# CI_Server_Wiring.net
KiCad netlist of a schematic drawn in EAGLE
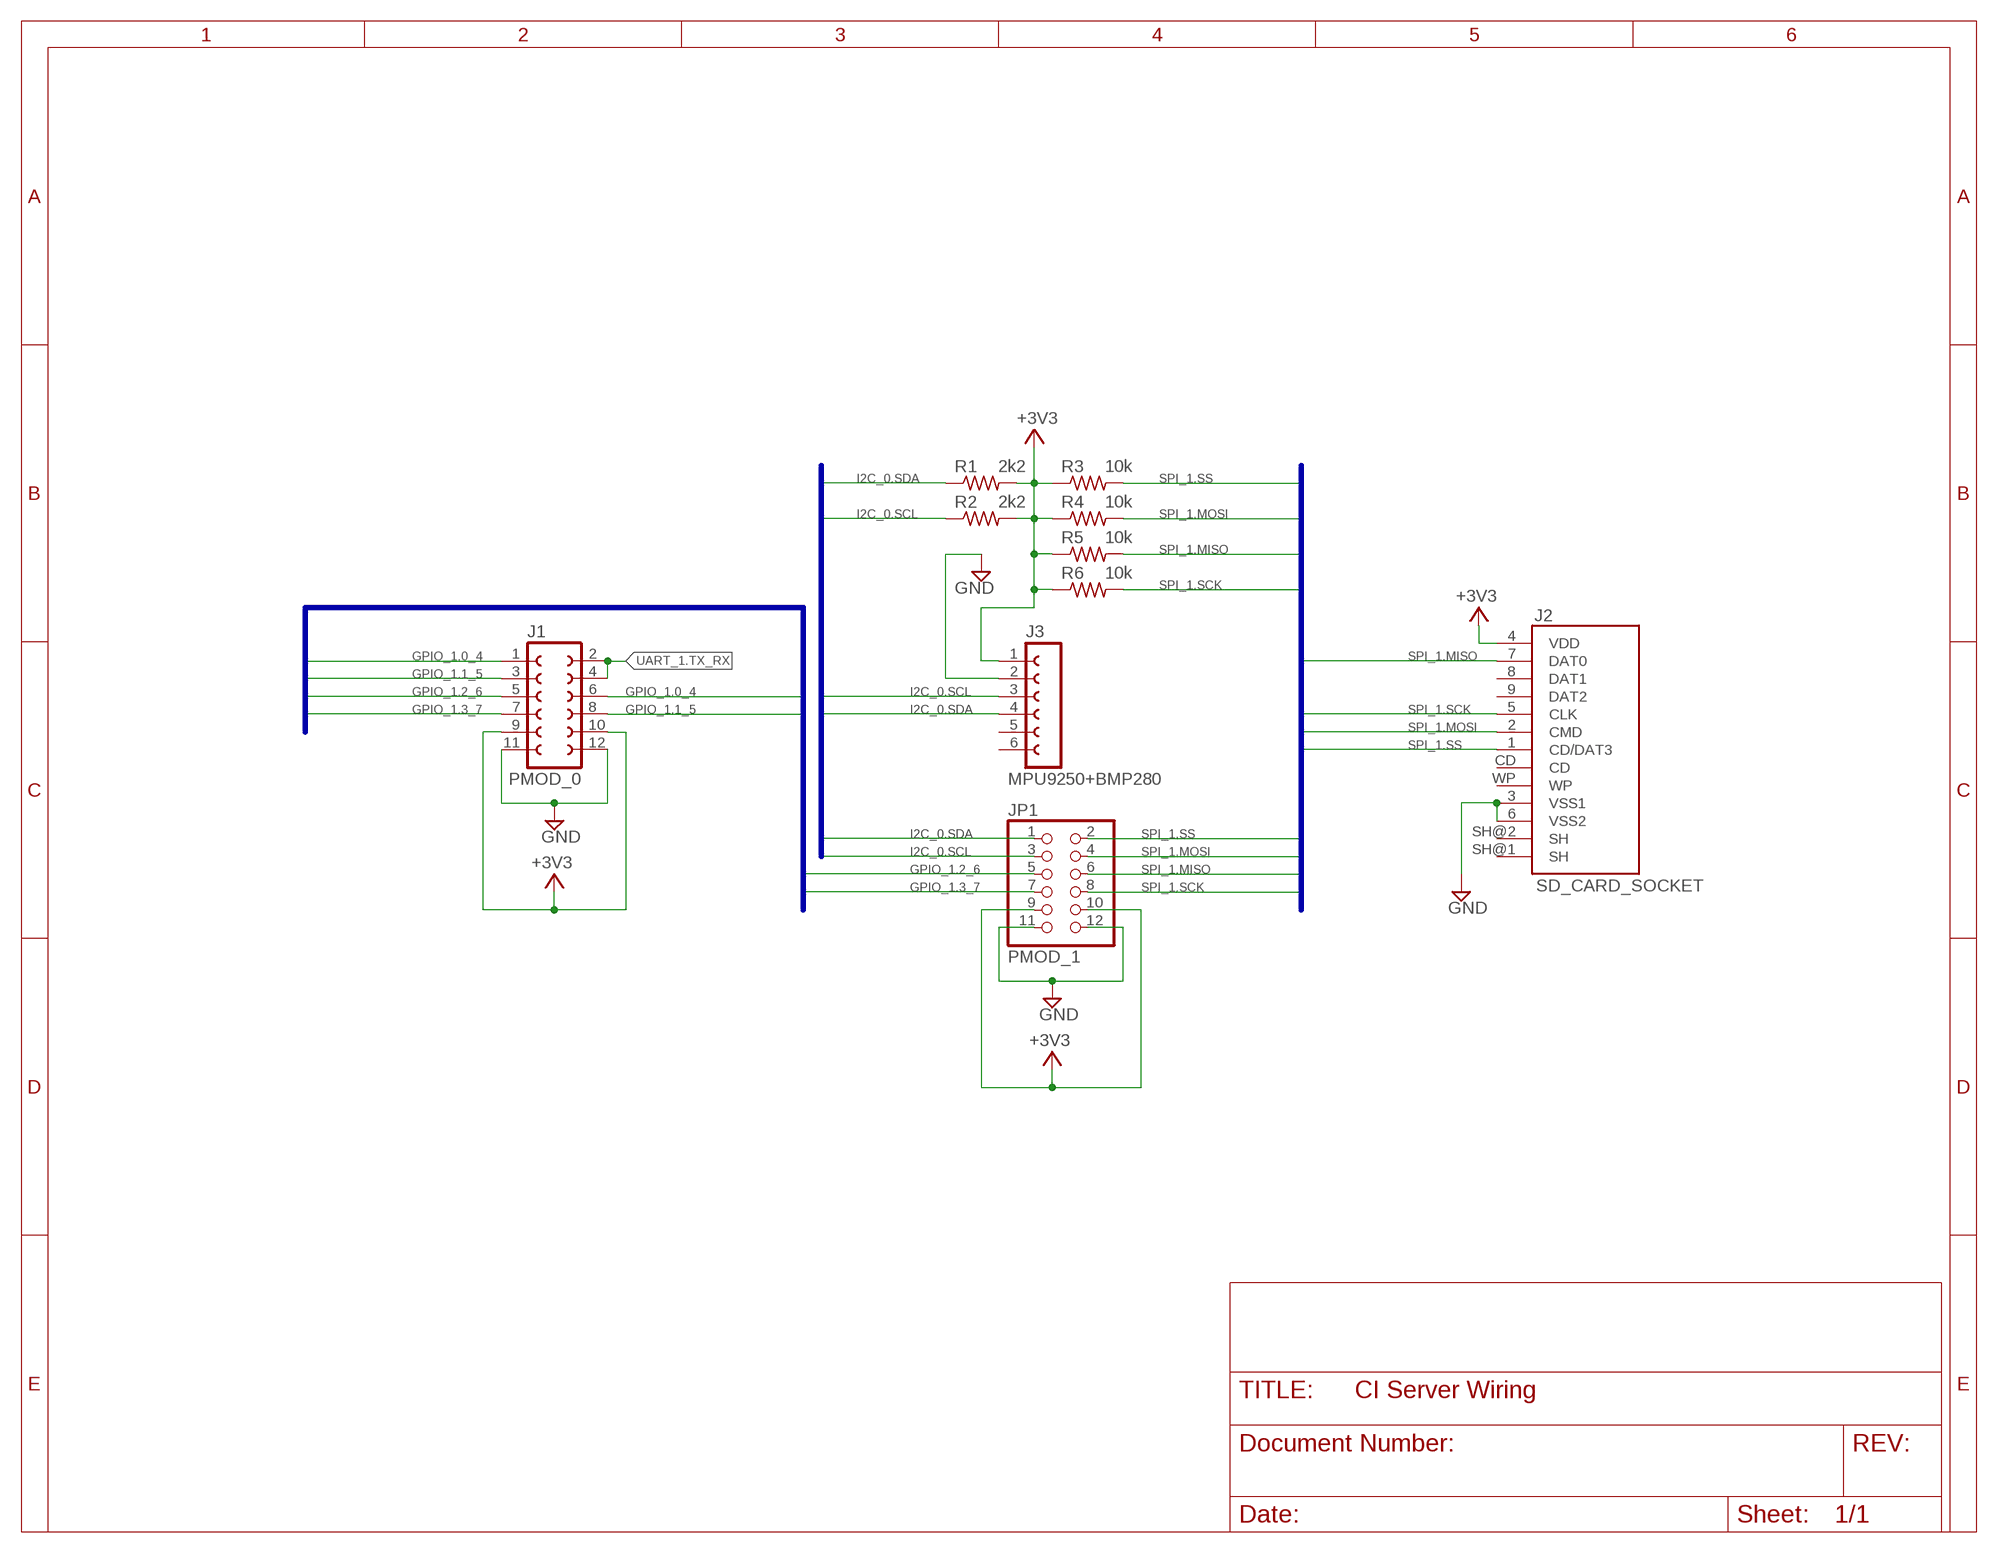
[diagram p0: schematic, sheet 1]

(export (version "E")
  (design (tool "Eeschema 10.0.6"))
  (components
    (comp (ref "J1")
      (value "PMOD_0")
      (footprint "eagle-import:FE06-2W")
      (libsource (lib "eagle-import") (part "FE06-2W"))
    )
    (comp (ref "J2")
      (value "SD_CARD_SOCKET")
      (footprint "eagle-import:SD")
      (libsource (lib "eagle-import") (part "SD_CARD_SOCKET"))
    )
    (comp (ref "J3")
      (value "MPU9250+BMP280")
      (footprint "eagle-import:FE06")
      (libsource (lib "eagle-import") (part "FE06-1"))
    )
    (comp (ref "JP1")
      (value "PMOD_1")
      (footprint "eagle-import:2X06_90")
      (libsource (lib "eagle-import") (part "PINHD-2X6/90"))
    )
    (comp (ref "R1")
      (value "2k2")
      (footprint "eagle-import:0309_12")
      (libsource (lib "eagle-import") (part "R-US_0309/12"))
    )
    (comp (ref "R2")
      (value "2k2")
      (footprint "eagle-import:0309_12")
      (libsource (lib "eagle-import") (part "R-US_0309/12"))
    )
    (comp (ref "R3")
      (value "10k")
      (footprint "eagle-import:0309_12")
      (libsource (lib "eagle-import") (part "R-US_0309/12"))
    )
    (comp (ref "R4")
      (value "10k")
      (footprint "eagle-import:0309_12")
      (libsource (lib "eagle-import") (part "R-US_0309/12"))
    )
    (comp (ref "R5")
      (value "10k")
      (footprint "eagle-import:0309_12")
      (libsource (lib "eagle-import") (part "R-US_0309/12"))
    )
    (comp (ref "R6")
      (value "10k")
      (footprint "eagle-import:0309_12")
      (libsource (lib "eagle-import") (part "R-US_0309/12"))
    )
  )
  (nets
    (net (code "1") (name "+3V3") (class "Default")
      (node (ref "J1") (pin "10") (pinfunction "10_10") (pintype "passive"))
      (node (ref "J1") (pin "9") (pinfunction "9_9") (pintype "passive"))
      (node (ref "J2") (pin "4") (pinfunction "VDD_4") (pintype "power_in"))
      (node (ref "J3") (pin "1") (pinfunction "1_1") (pintype "passive"))
      (node (ref "JP1") (pin "10") (pinfunction "10_10") (pintype "passive"))
      (node (ref "JP1") (pin "9") (pinfunction "9_9") (pintype "passive"))
      (node (ref "R1") (pin "2") (pinfunction "2_2") (pintype "passive"))
      (node (ref "R2") (pin "2") (pinfunction "2_2") (pintype "passive"))
      (node (ref "R3") (pin "1") (pinfunction "1_1") (pintype "passive"))
      (node (ref "R4") (pin "1") (pinfunction "1_1") (pintype "passive"))
      (node (ref "R5") (pin "1") (pinfunction "1_1") (pintype "passive"))
      (node (ref "R6") (pin "1") (pinfunction "1_1") (pintype "passive"))
    )
    (net (code "2") (name "/GPIO_1.0_4") (class "Default")
      (node (ref "J1") (pin "1") (pinfunction "1_1") (pintype "passive"))
      (node (ref "J1") (pin "6") (pinfunction "6_6") (pintype "passive"))
    )
    (net (code "3") (name "/GPIO_1.1_5") (class "Default")
      (node (ref "J1") (pin "3") (pinfunction "3_3") (pintype "passive"))
      (node (ref "J1") (pin "8") (pinfunction "8_8") (pintype "passive"))
    )
    (net (code "4") (name "/GPIO_1.2_6") (class "Default")
      (node (ref "J1") (pin "5") (pinfunction "5_5") (pintype "passive"))
      (node (ref "JP1") (pin "5") (pinfunction "5_5") (pintype "passive"))
    )
    (net (code "5") (name "/GPIO_1.3_7") (class "Default")
      (node (ref "J1") (pin "7") (pinfunction "7_7") (pintype "passive"))
      (node (ref "JP1") (pin "7") (pinfunction "7_7") (pintype "passive"))
    )
    (net (code "6") (name "/I2C_0.SCL") (class "Default")
      (node (ref "J3") (pin "3") (pinfunction "3_3") (pintype "passive"))
      (node (ref "JP1") (pin "3") (pinfunction "3_3") (pintype "passive"))
      (node (ref "R2") (pin "1") (pinfunction "1_1") (pintype "passive"))
    )
    (net (code "7") (name "/I2C_0.SDA") (class "Default")
      (node (ref "J3") (pin "4") (pinfunction "4_4") (pintype "passive"))
      (node (ref "JP1") (pin "1") (pinfunction "1_1") (pintype "passive"))
      (node (ref "R1") (pin "1") (pinfunction "1_1") (pintype "passive"))
    )
    (net (code "8") (name "/SPI_1.MISO") (class "Default")
      (node (ref "J2") (pin "7") (pinfunction "DAT0_7") (pintype "bidirectional"))
      (node (ref "JP1") (pin "6") (pinfunction "6_6") (pintype "passive"))
      (node (ref "R5") (pin "2") (pinfunction "2_2") (pintype "passive"))
    )
    (net (code "9") (name "/SPI_1.MOSI") (class "Default")
      (node (ref "J2") (pin "2") (pinfunction "CMD_2") (pintype "bidirectional"))
      (node (ref "JP1") (pin "4") (pinfunction "4_4") (pintype "passive"))
      (node (ref "R4") (pin "2") (pinfunction "2_2") (pintype "passive"))
    )
    (net (code "10") (name "/SPI_1.SCK") (class "Default")
      (node (ref "J2") (pin "5") (pinfunction "CLK_5") (pintype "bidirectional"))
      (node (ref "JP1") (pin "8") (pinfunction "8_8") (pintype "passive"))
      (node (ref "R6") (pin "2") (pinfunction "2_2") (pintype "passive"))
    )
    (net (code "11") (name "/SPI_1.SS") (class "Default")
      (node (ref "J2") (pin "1") (pinfunction "CD/DAT3_1") (pintype "bidirectional"))
      (node (ref "JP1") (pin "2") (pinfunction "2_2") (pintype "passive"))
      (node (ref "R3") (pin "2") (pinfunction "2_2") (pintype "passive"))
    )
    (net (code "12") (name "GND") (class "Default")
      (node (ref "J1") (pin "11") (pinfunction "11_11") (pintype "passive"))
      (node (ref "J1") (pin "12") (pinfunction "12_12") (pintype "passive"))
      (node (ref "J2") (pin "3") (pinfunction "VSS1_3") (pintype "power_in"))
      (node (ref "J2") (pin "6") (pinfunction "VSS2_6") (pintype "power_in"))
      (node (ref "J3") (pin "2") (pinfunction "2_2") (pintype "passive"))
      (node (ref "JP1") (pin "11") (pinfunction "11_11") (pintype "passive"))
      (node (ref "JP1") (pin "12") (pinfunction "12_12") (pintype "passive"))
    )
    (net (code "13") (name "UART_1.TX_RX") (class "Default")
      (node (ref "J1") (pin "2") (pinfunction "2_2") (pintype "passive"))
      (node (ref "J1") (pin "4") (pinfunction "4_4") (pintype "passive"))
    )
    (net (code "14") (name "unconnected-(J2-DAT1-Pad8)") (class "Default")
      (node (ref "J2") (pin "8") (pinfunction "DAT1_8") (pintype "bidirectional"))
    )
    (net (code "15") (name "unconnected-(J2-DAT2-Pad9)") (class "Default")
      (node (ref "J2") (pin "9") (pinfunction "DAT2_9") (pintype "bidirectional"))
    )
    (net (code "16") (name "unconnected-(J2-PadCD)") (class "Default")
      (node (ref "J2") (pin "CD") (pinfunction "CD_CD") (pintype "bidirectional"))
    )
    (net (code "17") (name "unconnected-(J2-PadWP)") (class "Default")
      (node (ref "J2") (pin "WP") (pinfunction "WP_WP") (pintype "bidirectional"))
    )
    (net (code "18") (name "unconnected-(J2-SH-PadSH@1)") (class "Default")
      (node (ref "J2") (pin "SH@1") (pinfunction "SH_SH@1") (pintype "bidirectional"))
    )
    (net (code "19") (name "unconnected-(J2-SH-PadSH@2)") (class "Default")
      (node (ref "J2") (pin "SH@2") (pinfunction "SH_SH@2") (pintype "bidirectional"))
    )
    (net (code "20") (name "unconnected-(J3-Pad5)") (class "Default")
      (node (ref "J3") (pin "5") (pinfunction "5_5") (pintype "passive"))
    )
    (net (code "21") (name "unconnected-(J3-Pad6)") (class "Default")
      (node (ref "J3") (pin "6") (pinfunction "6_6") (pintype "passive"))
    )
  )
)
